# control_board.net
KiCad netlist of a schematic drawn in EAGLE
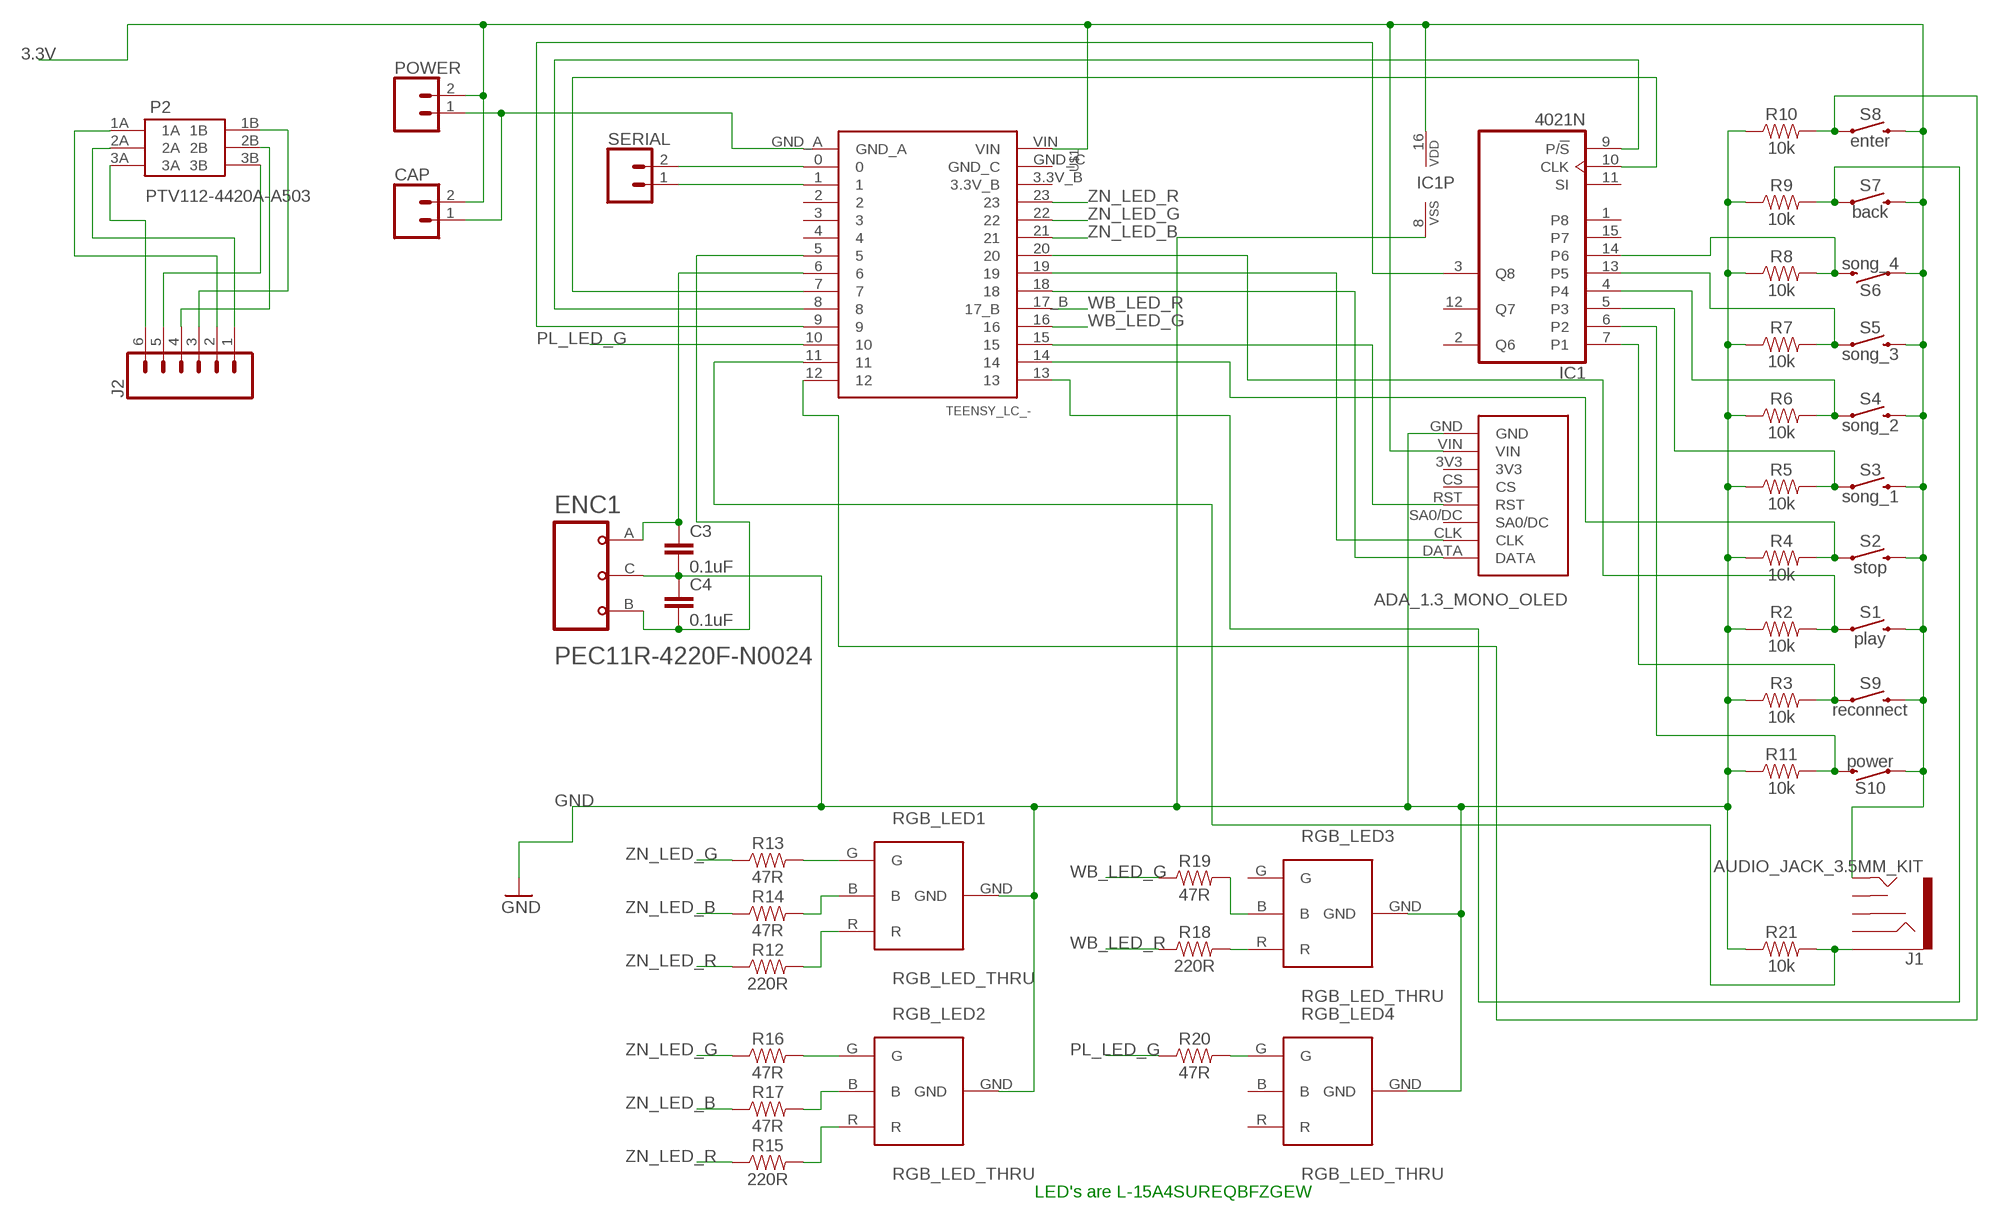
[diagram p0: schematic, sheet 1]

(export (version "E")
  (design (tool "Eeschema 10.0.6"))
  (components
    (comp (ref "C3")
      (value "0.1uF")
      (footprint "eagle-import:CAP-PTH-SMALL-KIT")
      (libsource (lib "eagle-import") (part "0.1UF-KIT-EZ-50V-20%"))
    )
    (comp (ref "C4")
      (value "0.1uF")
      (footprint "eagle-import:CAP-PTH-SMALL-KIT")
      (libsource (lib "eagle-import") (part "0.1UF-KIT-EZ-50V-20%"))
    )
    (comp (ref "CAP")
      (value "CONN_02")
      (footprint "eagle-import:1X02")
      (libsource (lib "eagle-import") (part "CONN_02"))
    )
    (comp (ref "ENC1")
      (value "PEC11R-4220F-N0024")
      (footprint "eagle-import:PEC11R-4220F-N0024")
      (libsource (lib "eagle-import") (part "PEC11R-4220F-N0024"))
    )
    (comp (ref "IC1")
      (value "4021N")
      (footprint "eagle-import:DIL16")
      (libsource (lib "eagle-import") (part "4021N"))
    )
    (comp (ref "J1")
      (value "AUDIO_JACK_3.5MM_KIT")
      (footprint "eagle-import:AUDIO-JACK-KIT")
      (libsource (lib "eagle-import") (part "AUDIO_JACK_3.5MM_KIT"))
    )
    (comp (ref "J2")
      (value "CONN_06NO_SILK_NO_POP")
      (footprint "eagle-import:1X06_NO_SILK")
      (libsource (lib "eagle-import") (part "CONN_06NO_SILK_NO_POP"))
    )
    (comp (ref "OLED1")
      (value "ADA_1.3_MONO_OLED")
      (footprint "eagle-import:ADA_1.3_MONO_OLED")
      (libsource (lib "eagle-import") (part "ADA_1.3_MONO_OLED"))
    )
    (comp (ref "P2")
      (value "PTV112-4420A-A503")
      (footprint "eagle-import:PTV122-4420A-A503")
      (libsource (lib "eagle-import") (part "PTV112-4420A-A503"))
    )
    (comp (ref "POWER")
      (value "CONN_02")
      (footprint "eagle-import:1X02")
      (libsource (lib "eagle-import") (part "CONN_02"))
    )
    (comp (ref "R2")
      (value "10k")
      (footprint "eagle-import:AXIAL-0.3")
      (libsource (lib "eagle-import") (part "10KOHM-HORIZ-1/4W-1%"))
    )
    (comp (ref "R3")
      (value "10k")
      (footprint "eagle-import:AXIAL-0.3")
      (libsource (lib "eagle-import") (part "10KOHM-HORIZ-1/4W-1%"))
    )
    (comp (ref "R4")
      (value "10k")
      (footprint "eagle-import:AXIAL-0.3")
      (libsource (lib "eagle-import") (part "10KOHM-HORIZ-1/4W-1%"))
    )
    (comp (ref "R5")
      (value "10k")
      (footprint "eagle-import:AXIAL-0.3")
      (libsource (lib "eagle-import") (part "10KOHM-HORIZ-1/4W-1%"))
    )
    (comp (ref "R6")
      (value "10k")
      (footprint "eagle-import:AXIAL-0.3")
      (libsource (lib "eagle-import") (part "10KOHM-HORIZ-1/4W-1%"))
    )
    (comp (ref "R7")
      (value "10k")
      (footprint "eagle-import:AXIAL-0.3")
      (libsource (lib "eagle-import") (part "10KOHM-HORIZ-1/4W-1%"))
    )
    (comp (ref "R8")
      (value "10k")
      (footprint "eagle-import:AXIAL-0.3")
      (libsource (lib "eagle-import") (part "10KOHM-HORIZ-1/4W-1%"))
    )
    (comp (ref "R9")
      (value "10k")
      (footprint "eagle-import:AXIAL-0.3")
      (libsource (lib "eagle-import") (part "10KOHM-HORIZ-1/4W-1%"))
    )
    (comp (ref "R10")
      (value "10k")
      (footprint "eagle-import:AXIAL-0.3")
      (libsource (lib "eagle-import") (part "10KOHM-HORIZ-1/4W-1%"))
    )
    (comp (ref "R11")
      (value "10k")
      (footprint "eagle-import:AXIAL-0.3")
      (libsource (lib "eagle-import") (part "10KOHM-HORIZ-1/4W-1%"))
    )
    (comp (ref "R12")
      (value "220R")
      (footprint "eagle-import:AXIAL-0.3")
      (libsource (lib "eagle-import") (part "100OHM-HORIZ-1/4W-1%"))
    )
    (comp (ref "R13")
      (value "47R")
      (footprint "eagle-import:AXIAL-0.3")
      (libsource (lib "eagle-import") (part "100OHM-HORIZ-1/4W-1%"))
    )
    (comp (ref "R14")
      (value "47R")
      (footprint "eagle-import:AXIAL-0.3")
      (libsource (lib "eagle-import") (part "100OHM-HORIZ-1/4W-1%"))
    )
    (comp (ref "R15")
      (value "220R")
      (footprint "eagle-import:AXIAL-0.3")
      (libsource (lib "eagle-import") (part "100OHM-HORIZ-1/4W-1%"))
    )
    (comp (ref "R16")
      (value "47R")
      (footprint "eagle-import:AXIAL-0.3")
      (libsource (lib "eagle-import") (part "100OHM-HORIZ-1/4W-1%"))
    )
    (comp (ref "R17")
      (value "47R")
      (footprint "eagle-import:AXIAL-0.3")
      (libsource (lib "eagle-import") (part "100OHM-HORIZ-1/4W-1%"))
    )
    (comp (ref "R18")
      (value "220R")
      (footprint "eagle-import:AXIAL-0.3")
      (libsource (lib "eagle-import") (part "100OHM-HORIZ-1/4W-1%"))
    )
    (comp (ref "R19")
      (value "47R")
      (footprint "eagle-import:AXIAL-0.3")
      (libsource (lib "eagle-import") (part "100OHM-HORIZ-1/4W-1%"))
    )
    (comp (ref "R20")
      (value "47R")
      (footprint "eagle-import:AXIAL-0.3")
      (libsource (lib "eagle-import") (part "100OHM-HORIZ-1/4W-1%"))
    )
    (comp (ref "R21")
      (value "10k")
      (footprint "eagle-import:AXIAL-0.3")
      (libsource (lib "eagle-import") (part "10KOHM-HORIZ-1/4W-1%"))
    )
    (comp (ref "RGB_LED1")
      (value "RGB_LED_THRU")
      (footprint "eagle-import:RGB_LEB_RGB_2")
      (libsource (lib "eagle-import") (part "RGB_LED_THRU"))
    )
    (comp (ref "RGB_LED2")
      (value "RGB_LED_THRU")
      (footprint "eagle-import:RGB_LEB_RGB_2")
      (libsource (lib "eagle-import") (part "RGB_LED_THRU"))
    )
    (comp (ref "RGB_LED3")
      (value "RGB_LED_THRU")
      (footprint "eagle-import:RGB_LEB_RGB_2")
      (libsource (lib "eagle-import") (part "RGB_LED_THRU"))
    )
    (comp (ref "RGB_LED4")
      (value "RGB_LED_THRU")
      (footprint "eagle-import:RGB_LEB_RGB_2")
      (libsource (lib "eagle-import") (part "RGB_LED_THRU"))
    )
    (comp (ref "S1")
      (value "play")
      (footprint "eagle-import:TACTILE_SWITCH_PTH_6.0MM")
      (libsource (lib "eagle-import") (part "MOMENTARY-SWITCH-SPST-PTH-6.0MM"))
    )
    (comp (ref "S2")
      (value "stop")
      (footprint "eagle-import:TACTILE_SWITCH_PTH_6.0MM")
      (libsource (lib "eagle-import") (part "MOMENTARY-SWITCH-SPST-PTH-6.0MM"))
    )
    (comp (ref "S3")
      (value "song_1")
      (footprint "eagle-import:TACTILE_SWITCH_PTH_6.0MM")
      (libsource (lib "eagle-import") (part "MOMENTARY-SWITCH-SPST-PTH-6.0MM"))
    )
    (comp (ref "S4")
      (value "song_2")
      (footprint "eagle-import:TACTILE_SWITCH_PTH_6.0MM")
      (libsource (lib "eagle-import") (part "MOMENTARY-SWITCH-SPST-PTH-6.0MM"))
    )
    (comp (ref "S5")
      (value "song_3")
      (footprint "eagle-import:TACTILE_SWITCH_PTH_6.0MM")
      (libsource (lib "eagle-import") (part "MOMENTARY-SWITCH-SPST-PTH-6.0MM"))
    )
    (comp (ref "S6")
      (value "song_4")
      (footprint "eagle-import:TACTILE_SWITCH_PTH_6.0MM")
      (libsource (lib "eagle-import") (part "MOMENTARY-SWITCH-SPST-PTH-6.0MM"))
    )
    (comp (ref "S7")
      (value "back")
      (footprint "eagle-import:TACTILE_SWITCH_PTH_6.0MM")
      (libsource (lib "eagle-import") (part "MOMENTARY-SWITCH-SPST-PTH-6.0MM"))
    )
    (comp (ref "S8")
      (value "enter")
      (footprint "eagle-import:TACTILE_SWITCH_PTH_6.0MM")
      (libsource (lib "eagle-import") (part "MOMENTARY-SWITCH-SPST-PTH-6.0MM"))
    )
    (comp (ref "S9")
      (value "reconnect")
      (footprint "eagle-import:TACTILE_SWITCH_PTH_6.0MM")
      (libsource (lib "eagle-import") (part "MOMENTARY-SWITCH-SPST-PTH-6.0MM"))
    )
    (comp (ref "S10")
      (value "power")
      (footprint "eagle-import:TACTILE_SWITCH_PTH_6.0MM")
      (libsource (lib "eagle-import") (part "MOMENTARY-SWITCH-SPST-PTH-6.0MM"))
    )
    (comp (ref "SERIAL")
      (value "CONN_02")
      (footprint "eagle-import:1X02")
      (libsource (lib "eagle-import") (part "CONN_02"))
    )
    (comp (ref "U$1")
      (value "TEENSY_LC_-")
      (footprint "eagle-import:TEENSY_LC_-")
      (libsource (lib "eagle-import") (part "TEENSY_LC_-"))
    )
  )
  (nets
    (net (code "1") (name "/3.3V") (class "Default")
      (node (ref "CAP") (pin "2") (pinfunction "2_2") (pintype "passive"))
      (node (ref "IC1") (pin "16") (pinfunction "VDD_16") (pintype "power_in"))
      (node (ref "J1") (pin "TIP") (pinfunction "TIP_TIP") (pintype "bidirectional"))
      (node (ref "OLED1") (pin "VIN") (pinfunction "VIN_VIN") (pintype "bidirectional"))
      (node (ref "POWER") (pin "2") (pinfunction "2_2") (pintype "passive"))
      (node (ref "S1") (pin "3") (pinfunction "2_3") (pintype "passive"))
      (node (ref "S10") (pin "1") (pinfunction "1_1") (pintype "passive"))
      (node (ref "S2") (pin "3") (pinfunction "2_3") (pintype "passive"))
      (node (ref "S3") (pin "3") (pinfunction "2_3") (pintype "passive"))
      (node (ref "S4") (pin "3") (pinfunction "2_3") (pintype "passive"))
      (node (ref "S5") (pin "3") (pinfunction "2_3") (pintype "passive"))
      (node (ref "S6") (pin "1") (pinfunction "1_1") (pintype "passive"))
      (node (ref "S7") (pin "3") (pinfunction "2_3") (pintype "passive"))
      (node (ref "S8") (pin "3") (pinfunction "2_3") (pintype "passive"))
      (node (ref "S9") (pin "3") (pinfunction "2_3") (pintype "passive"))
      (node (ref "U$1") (pin "VIN") (pinfunction "VIN_VIN") (pintype "bidirectional"))
    )
    (net (code "2") (name "/PL_LED_G") (class "Default")
      (node (ref "R20") (pin "P$1") (pinfunction "1_P$1") (pintype "passive"))
      (node (ref "U$1") (pin "10") (pinfunction "10_10") (pintype "bidirectional"))
    )
    (net (code "3") (name "/WB_LED_G") (class "Default")
      (node (ref "R19") (pin "P$1") (pinfunction "1_P$1") (pintype "passive"))
      (node (ref "U$1") (pin "16") (pinfunction "16_16") (pintype "bidirectional"))
    )
    (net (code "4") (name "/WB_LED_R") (class "Default")
      (node (ref "R18") (pin "P$1") (pinfunction "1_P$1") (pintype "passive"))
      (node (ref "U$1") (pin "17_B") (pinfunction "17_B_17_B") (pintype "bidirectional"))
    )
    (net (code "5") (name "/ZN_LED_B") (class "Default")
      (node (ref "R14") (pin "P$1") (pinfunction "1_P$1") (pintype "passive"))
      (node (ref "R17") (pin "P$1") (pinfunction "1_P$1") (pintype "passive"))
      (node (ref "U$1") (pin "21") (pinfunction "21_21") (pintype "bidirectional"))
    )
    (net (code "6") (name "/ZN_LED_G") (class "Default")
      (node (ref "R13") (pin "P$1") (pinfunction "1_P$1") (pintype "passive"))
      (node (ref "R16") (pin "P$1") (pinfunction "1_P$1") (pintype "passive"))
      (node (ref "U$1") (pin "22") (pinfunction "22_22") (pintype "bidirectional"))
    )
    (net (code "7") (name "/ZN_LED_R") (class "Default")
      (node (ref "R12") (pin "P$1") (pinfunction "1_P$1") (pintype "passive"))
      (node (ref "R15") (pin "P$1") (pinfunction "1_P$1") (pintype "passive"))
      (node (ref "U$1") (pin "23") (pinfunction "23_23") (pintype "bidirectional"))
    )
    (net (code "8") (name "GND") (class "Default")
      (node (ref "C3") (pin "2") (pinfunction "2_2") (pintype "passive"))
      (node (ref "C4") (pin "1") (pinfunction "1_1") (pintype "passive"))
      (node (ref "CAP") (pin "1") (pinfunction "1_1") (pintype "passive"))
      (node (ref "ENC1") (pin "C") (pinfunction "COMMON_C") (pintype "bidirectional"))
      (node (ref "IC1") (pin "8") (pinfunction "VSS_8") (pintype "power_in"))
      (node (ref "OLED1") (pin "GND") (pinfunction "GND_GND") (pintype "bidirectional"))
      (node (ref "POWER") (pin "1") (pinfunction "1_1") (pintype "passive"))
      (node (ref "R10") (pin "P$1") (pinfunction "1_P$1") (pintype "passive"))
      (node (ref "R11") (pin "P$1") (pinfunction "1_P$1") (pintype "passive"))
      (node (ref "R2") (pin "P$1") (pinfunction "1_P$1") (pintype "passive"))
      (node (ref "R21") (pin "P$1") (pinfunction "1_P$1") (pintype "passive"))
      (node (ref "R3") (pin "P$1") (pinfunction "1_P$1") (pintype "passive"))
      (node (ref "R4") (pin "P$1") (pinfunction "1_P$1") (pintype "passive"))
      (node (ref "R5") (pin "P$1") (pinfunction "1_P$1") (pintype "passive"))
      (node (ref "R6") (pin "P$1") (pinfunction "1_P$1") (pintype "passive"))
      (node (ref "R7") (pin "P$1") (pinfunction "1_P$1") (pintype "passive"))
      (node (ref "R8") (pin "P$1") (pinfunction "1_P$1") (pintype "passive"))
      (node (ref "R9") (pin "P$1") (pinfunction "1_P$1") (pintype "passive"))
      (node (ref "RGB_LED1") (pin "GND") (pinfunction "GND_GND") (pintype "bidirectional"))
      (node (ref "RGB_LED2") (pin "GND") (pinfunction "GND_GND") (pintype "bidirectional"))
      (node (ref "RGB_LED3") (pin "GND") (pinfunction "GND_GND") (pintype "bidirectional"))
      (node (ref "RGB_LED4") (pin "GND") (pinfunction "GND_GND") (pintype "bidirectional"))
      (node (ref "U$1") (pin "GND_A") (pinfunction "GND_A_GND_A") (pintype "bidirectional"))
    )
    (net (code "9") (name "Net-(ENC1-CHANNEL_A)") (class "Default")
      (node (ref "C3") (pin "1") (pinfunction "1_1") (pintype "passive"))
      (node (ref "ENC1") (pin "A") (pinfunction "CHANNEL_A_A") (pintype "bidirectional"))
      (node (ref "U$1") (pin "6") (pinfunction "6_6") (pintype "bidirectional"))
    )
    (net (code "10") (name "Net-(ENC1-COMMON_B)") (class "Default")
      (node (ref "C4") (pin "2") (pinfunction "2_2") (pintype "passive"))
      (node (ref "ENC1") (pin "B") (pinfunction "COMMON_B_B") (pintype "bidirectional"))
      (node (ref "U$1") (pin "5") (pinfunction "5_5") (pintype "bidirectional"))
    )
    (net (code "11") (name "Net-(IC1A-CLK)") (class "Default")
      (node (ref "IC1") (pin "10") (pinfunction "CLK_10") (pintype "input"))
      (node (ref "U$1") (pin "7") (pinfunction "7_7") (pintype "bidirectional"))
    )
    (net (code "12") (name "Net-(IC1A-P1)") (class "Default")
      (node (ref "IC1") (pin "7") (pinfunction "P1_7") (pintype "input"))
      (node (ref "R3") (pin "P$2") (pinfunction "2_P$2") (pintype "passive"))
      (node (ref "S9") (pin "1") (pinfunction "1_1") (pintype "passive"))
    )
    (net (code "13") (name "Net-(IC1A-P2)") (class "Default")
      (node (ref "IC1") (pin "6") (pinfunction "P2_6") (pintype "input"))
      (node (ref "R11") (pin "P$2") (pinfunction "2_P$2") (pintype "passive"))
      (node (ref "S10") (pin "3") (pinfunction "2_3") (pintype "passive"))
    )
    (net (code "14") (name "Net-(IC1A-P3)") (class "Default")
      (node (ref "IC1") (pin "5") (pinfunction "P3_5") (pintype "input"))
      (node (ref "R5") (pin "P$2") (pinfunction "2_P$2") (pintype "passive"))
      (node (ref "S3") (pin "1") (pinfunction "1_1") (pintype "passive"))
    )
    (net (code "15") (name "Net-(IC1A-P4)") (class "Default")
      (node (ref "IC1") (pin "4") (pinfunction "P4_4") (pintype "input"))
      (node (ref "R6") (pin "P$2") (pinfunction "2_P$2") (pintype "passive"))
      (node (ref "S4") (pin "1") (pinfunction "1_1") (pintype "passive"))
    )
    (net (code "16") (name "Net-(IC1A-P5)") (class "Default")
      (node (ref "IC1") (pin "13") (pinfunction "P5_13") (pintype "input"))
      (node (ref "R7") (pin "P$2") (pinfunction "2_P$2") (pintype "passive"))
      (node (ref "S5") (pin "1") (pinfunction "1_1") (pintype "passive"))
    )
    (net (code "17") (name "Net-(IC1A-P6)") (class "Default")
      (node (ref "IC1") (pin "14") (pinfunction "P6_14") (pintype "input"))
      (node (ref "R8") (pin "P$2") (pinfunction "2_P$2") (pintype "passive"))
      (node (ref "S6") (pin "3") (pinfunction "2_3") (pintype "passive"))
    )
    (net (code "18") (name "Net-(IC1A-P{slash}~{S})") (class "Default")
      (node (ref "IC1") (pin "9") (pinfunction "P/~{S}_9") (pintype "input"))
      (node (ref "U$1") (pin "8") (pinfunction "8_8") (pintype "bidirectional"))
    )
    (net (code "19") (name "Net-(IC1A-Q8)") (class "Default")
      (node (ref "IC1") (pin "3") (pinfunction "Q8_3") (pintype "output"))
      (node (ref "U$1") (pin "9") (pinfunction "9_9") (pintype "bidirectional"))
    )
    (net (code "20") (name "Net-(J2-Pad1)") (class "Default")
      (node (ref "J2") (pin "1") (pinfunction "1_1") (pintype "passive"))
      (node (ref "P2") (pin "2A") (pinfunction "2A_2A") (pintype "bidirectional"))
    )
    (net (code "21") (name "Net-(J2-Pad2)") (class "Default")
      (node (ref "J2") (pin "2") (pinfunction "2_2") (pintype "passive"))
      (node (ref "P2") (pin "1A") (pinfunction "1A_1A") (pintype "bidirectional"))
    )
    (net (code "22") (name "Net-(J2-Pad3)") (class "Default")
      (node (ref "J2") (pin "3") (pinfunction "3_3") (pintype "passive"))
      (node (ref "P2") (pin "1B") (pinfunction "1B_1B") (pintype "bidirectional"))
    )
    (net (code "23") (name "Net-(J2-Pad4)") (class "Default")
      (node (ref "J2") (pin "4") (pinfunction "4_4") (pintype "passive"))
      (node (ref "P2") (pin "2B") (pinfunction "2B_2B") (pintype "bidirectional"))
    )
    (net (code "24") (name "Net-(J2-Pad5)") (class "Default")
      (node (ref "J2") (pin "5") (pinfunction "5_5") (pintype "passive"))
      (node (ref "P2") (pin "3B") (pinfunction "3B_3B") (pintype "bidirectional"))
    )
    (net (code "25") (name "Net-(J2-Pad6)") (class "Default")
      (node (ref "J2") (pin "6") (pinfunction "6_6") (pintype "passive"))
      (node (ref "P2") (pin "3A") (pinfunction "3A_3A") (pintype "bidirectional"))
    )
    (net (code "26") (name "Net-(OLED1-PadCLK)") (class "Default")
      (node (ref "OLED1") (pin "CLK") (pinfunction "CLK_CLK") (pintype "bidirectional"))
      (node (ref "U$1") (pin "19") (pinfunction "19_19") (pintype "bidirectional"))
    )
    (net (code "27") (name "Net-(OLED1-PadDATA)") (class "Default")
      (node (ref "OLED1") (pin "DATA") (pinfunction "DATA_DATA") (pintype "bidirectional"))
      (node (ref "U$1") (pin "18") (pinfunction "18_18") (pintype "bidirectional"))
    )
    (net (code "28") (name "Net-(OLED1-PadRST)") (class "Default")
      (node (ref "OLED1") (pin "RST") (pinfunction "RST_RST") (pintype "bidirectional"))
      (node (ref "U$1") (pin "15") (pinfunction "15_15") (pintype "bidirectional"))
    )
    (net (code "29") (name "Net-(R2-2)") (class "Default")
      (node (ref "R2") (pin "P$2") (pinfunction "2_P$2") (pintype "passive"))
      (node (ref "S1") (pin "1") (pinfunction "1_1") (pintype "passive"))
      (node (ref "U$1") (pin "20") (pinfunction "20_20") (pintype "bidirectional"))
    )
    (net (code "30") (name "Net-(R4-2)") (class "Default")
      (node (ref "R4") (pin "P$2") (pinfunction "2_P$2") (pintype "passive"))
      (node (ref "S2") (pin "1") (pinfunction "1_1") (pintype "passive"))
      (node (ref "U$1") (pin "14") (pinfunction "14_14") (pintype "bidirectional"))
    )
    (net (code "31") (name "Net-(R9-2)") (class "Default")
      (node (ref "R9") (pin "P$2") (pinfunction "2_P$2") (pintype "passive"))
      (node (ref "S7") (pin "1") (pinfunction "1_1") (pintype "passive"))
      (node (ref "U$1") (pin "13") (pinfunction "13_13") (pintype "bidirectional"))
    )
    (net (code "32") (name "Net-(R10-2)") (class "Default")
      (node (ref "R10") (pin "P$2") (pinfunction "2_P$2") (pintype "passive"))
      (node (ref "S8") (pin "1") (pinfunction "1_1") (pintype "passive"))
      (node (ref "U$1") (pin "12") (pinfunction "12_12") (pintype "bidirectional"))
    )
    (net (code "33") (name "Net-(R12-2)") (class "Default")
      (node (ref "R12") (pin "P$2") (pinfunction "2_P$2") (pintype "passive"))
      (node (ref "RGB_LED1") (pin "R") (pinfunction "R_R") (pintype "bidirectional"))
    )
    (net (code "34") (name "Net-(R13-2)") (class "Default")
      (node (ref "R13") (pin "P$2") (pinfunction "2_P$2") (pintype "passive"))
      (node (ref "RGB_LED1") (pin "G") (pinfunction "G_G") (pintype "bidirectional"))
    )
    (net (code "35") (name "Net-(R14-2)") (class "Default")
      (node (ref "R14") (pin "P$2") (pinfunction "2_P$2") (pintype "passive"))
      (node (ref "RGB_LED1") (pin "B") (pinfunction "B_B") (pintype "bidirectional"))
    )
    (net (code "36") (name "Net-(R15-2)") (class "Default")
      (node (ref "R15") (pin "P$2") (pinfunction "2_P$2") (pintype "passive"))
      (node (ref "RGB_LED2") (pin "R") (pinfunction "R_R") (pintype "bidirectional"))
    )
    (net (code "37") (name "Net-(R16-2)") (class "Default")
      (node (ref "R16") (pin "P$2") (pinfunction "2_P$2") (pintype "passive"))
      (node (ref "RGB_LED2") (pin "G") (pinfunction "G_G") (pintype "bidirectional"))
    )
    (net (code "38") (name "Net-(R17-2)") (class "Default")
      (node (ref "R17") (pin "P$2") (pinfunction "2_P$2") (pintype "passive"))
      (node (ref "RGB_LED2") (pin "B") (pinfunction "B_B") (pintype "bidirectional"))
    )
    (net (code "39") (name "Net-(R18-2)") (class "Default")
      (node (ref "R18") (pin "P$2") (pinfunction "2_P$2") (pintype "passive"))
      (node (ref "RGB_LED3") (pin "R") (pinfunction "R_R") (pintype "bidirectional"))
    )
    (net (code "40") (name "Net-(R19-2)") (class "Default")
      (node (ref "R19") (pin "P$2") (pinfunction "2_P$2") (pintype "passive"))
      (node (ref "RGB_LED3") (pin "B") (pinfunction "B_B") (pintype "bidirectional"))
    )
    (net (code "41") (name "Net-(R20-2)") (class "Default")
      (node (ref "R20") (pin "P$2") (pinfunction "2_P$2") (pintype "passive"))
      (node (ref "RGB_LED4") (pin "G") (pinfunction "G_G") (pintype "bidirectional"))
    )
    (net (code "42") (name "Net-(R21-2)") (class "Default")
      (node (ref "J1") (pin "SLEEVE") (pinfunction "SLEEVE_SLEEVE") (pintype "bidirectional"))
      (node (ref "R21") (pin "P$2") (pinfunction "2_P$2") (pintype "passive"))
      (node (ref "U$1") (pin "11") (pinfunction "11_11") (pintype "bidirectional"))
    )
    (net (code "43") (name "Net-(SERIAL-Pad1)") (class "Default")
      (node (ref "SERIAL") (pin "1") (pinfunction "1_1") (pintype "passive"))
      (node (ref "U$1") (pin "1") (pinfunction "1_1") (pintype "bidirectional"))
    )
    (net (code "44") (name "Net-(SERIAL-Pad2)") (class "Default")
      (node (ref "SERIAL") (pin "2") (pinfunction "2_2") (pintype "passive"))
      (node (ref "U$1") (pin "0") (pinfunction "0_0") (pintype "bidirectional"))
    )
    (net (code "45") (name "unconnected-(IC1A-P7-Pad15)") (class "Default")
      (node (ref "IC1") (pin "15") (pinfunction "P7_15") (pintype "input"))
    )
    (net (code "46") (name "unconnected-(IC1A-P8-Pad1)") (class "Default")
      (node (ref "IC1") (pin "1") (pinfunction "P8_1") (pintype "input"))
    )
    (net (code "47") (name "unconnected-(IC1A-Q6-Pad2)") (class "Default")
      (node (ref "IC1") (pin "2") (pinfunction "Q6_2") (pintype "output"))
    )
    (net (code "48") (name "unconnected-(IC1A-Q7-Pad12)") (class "Default")
      (node (ref "IC1") (pin "12") (pinfunction "Q7_12") (pintype "output"))
    )
    (net (code "49") (name "unconnected-(IC1A-SI-Pad11)") (class "Default")
      (node (ref "IC1") (pin "11") (pinfunction "SI_11") (pintype "input"))
    )
    (net (code "50") (name "unconnected-(J1-PadRING)") (class "Default")
      (node (ref "J1") (pin "RING") (pinfunction "RING_RING") (pintype "bidirectional"))
    )
    (net (code "51") (name "unconnected-(J1-PadRSH)") (class "Default")
      (node (ref "J1") (pin "RSH") (pinfunction "RSH_RSH") (pintype "bidirectional"))
    )
    (net (code "52") (name "unconnected-(J1-PadTSH)") (class "Default")
      (node (ref "J1") (pin "TSH") (pinfunction "TSH_TSH") (pintype "bidirectional"))
    )
    (net (code "53") (name "unconnected-(OLED1-Pad3V3)") (class "Default")
      (node (ref "OLED1") (pin "3V3") (pinfunction "3V3_3V3") (pintype "bidirectional"))
    )
    (net (code "54") (name "unconnected-(OLED1-PadCS)") (class "Default")
      (node (ref "OLED1") (pin "CS") (pinfunction "CS_CS") (pintype "bidirectional"))
    )
    (net (code "55") (name "unconnected-(OLED1-PadSA0{slash}DC)") (class "Default")
      (node (ref "OLED1") (pin "SA0/DC") (pinfunction "SA0/DC_SA0/DC") (pintype "bidirectional"))
    )
    (net (code "56") (name "unconnected-(RGB_LED3-PadG)") (class "Default")
      (node (ref "RGB_LED3") (pin "G") (pinfunction "G_G") (pintype "bidirectional"))
    )
    (net (code "57") (name "unconnected-(RGB_LED4-PadB)") (class "Default")
      (node (ref "RGB_LED4") (pin "B") (pinfunction "B_B") (pintype "bidirectional"))
    )
    (net (code "58") (name "unconnected-(RGB_LED4-PadR)") (class "Default")
      (node (ref "RGB_LED4") (pin "R") (pinfunction "R_R") (pintype "bidirectional"))
    )
    (net (code "59") (name "unconnected-(U$1-Pad2)") (class "Default")
      (node (ref "U$1") (pin "2") (pinfunction "2_2") (pintype "bidirectional"))
    )
    (net (code "60") (name "unconnected-(U$1-Pad3)") (class "Default")
      (node (ref "U$1") (pin "3") (pinfunction "3_3") (pintype "bidirectional"))
    )
    (net (code "61") (name "unconnected-(U$1-Pad3.3V_B)") (class "Default")
      (node (ref "U$1") (pin "3.3V_B") (pinfunction "3.3V_B_3.3V_B") (pintype "bidirectional"))
    )
    (net (code "62") (name "unconnected-(U$1-Pad4)") (class "Default")
      (node (ref "U$1") (pin "4") (pinfunction "4_4") (pintype "bidirectional"))
    )
    (net (code "63") (name "unconnected-(U$1-PadGND_C)") (class "Default")
      (node (ref "U$1") (pin "GND_C") (pinfunction "GND_C_GND_C") (pintype "bidirectional"))
    )
  )
)
